# Miscellaneous.net
KiCad netlist of a schematic drawn in Altium Designer
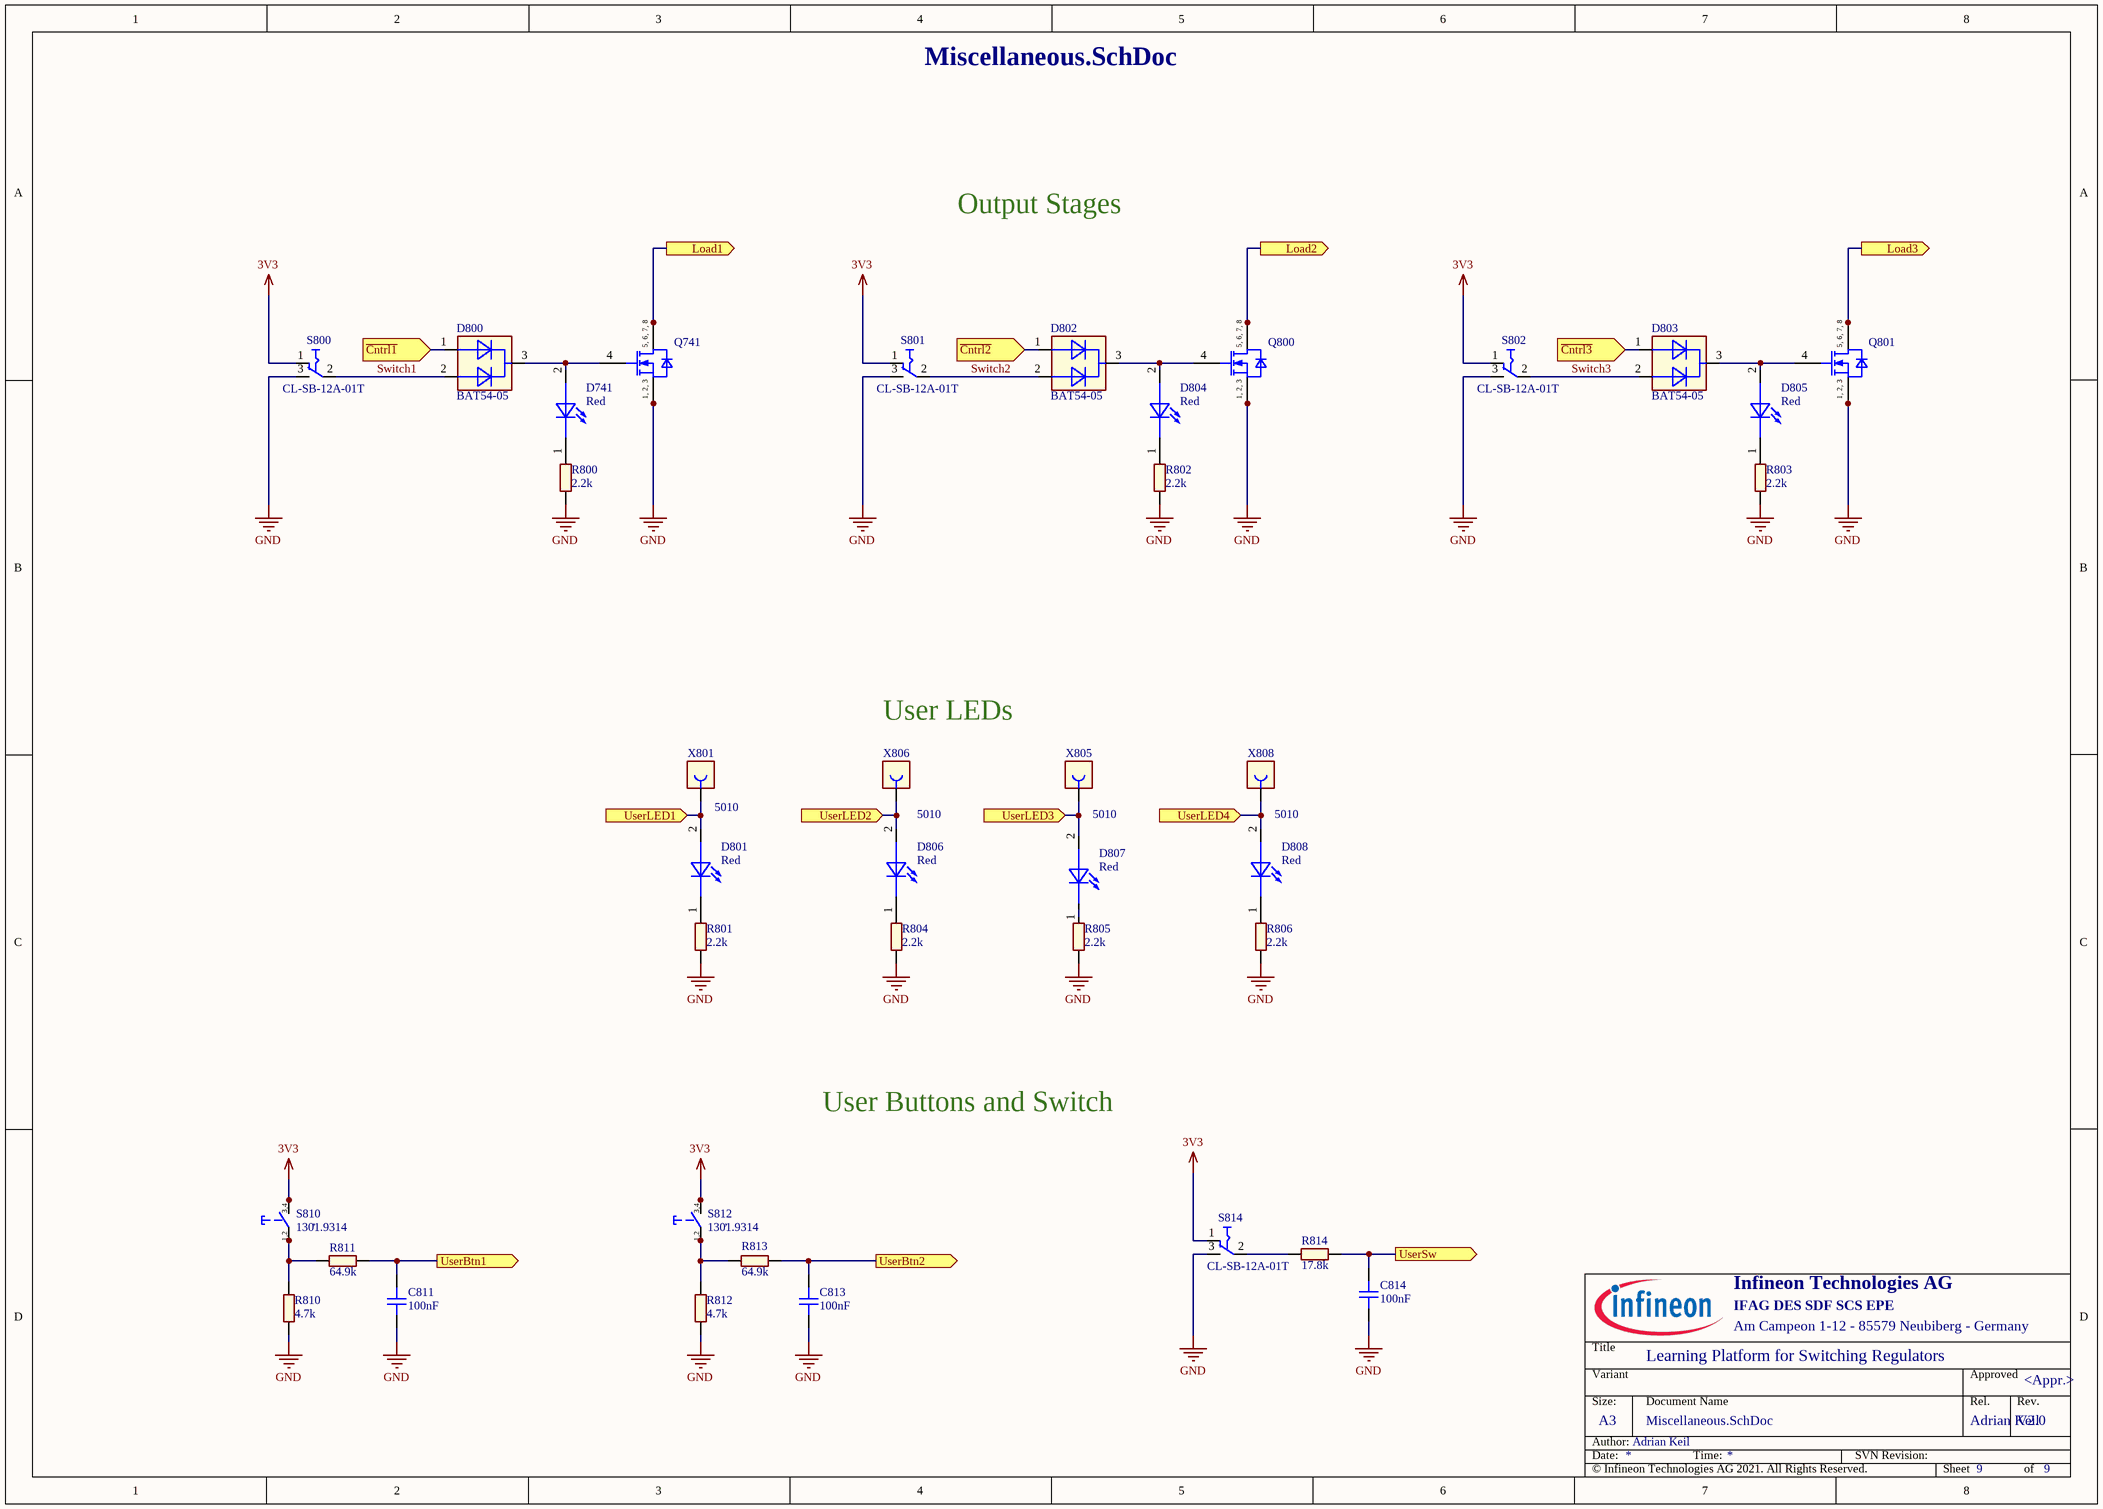
[diagram p0: Miscellaneous.SchDoc]

(export (version "E")
  (design (tool "Eeschema 10.0.6"))
  (components
    (comp (ref "C811")
      (value "100nF")
      (footprint "CAPC3216X125N-0")
      (description "CAP / CERA / 100nF / 50V / 10% / X7R (EIA) / -55°C to 125°C / 1206(3216) / SMD / -")
      (fields (field (name "LEGACY PARTNUMBER") "CAP01005660") (field (name "MANUFACTURER") "MuRata"))
      (libsource (lib "PCBLibraryData") (part "CAP-SGL-STD-02P_00000001"))
    )
    (comp (ref "C813")
      (value "100nF")
      (footprint "CAPC3216X125N-0")
      (description "CAP / CERA / 100nF / 50V / 10% / X7R (EIA) / -55°C to 125°C / 1206(3216) / SMD / -")
      (fields (field (name "LEGACY PARTNUMBER") "CAP01005660") (field (name "MANUFACTURER") "MuRata"))
      (libsource (lib "PCBLibraryData") (part "CAP-SGL-STD-02P_00000001"))
    )
    (comp (ref "C814")
      (value "100nF")
      (footprint "CAPC3216X125N-0")
      (description "CAP / CERA / 100nF / 50V / 10% / X7R (EIA) / -55°C to 125°C / 1206(3216) / SMD / -")
      (fields (field (name "LEGACY PARTNUMBER") "CAP01005660") (field (name "MANUFACTURER") "MuRata"))
      (libsource (lib "PCBLibraryData") (part "CAP-SGL-STD-02P_00000001"))
    )
    (comp (ref "D741")
      (value "Red")
      (footprint "LEDSC160X80X80-2N-1")
      (description "WL-SMCW SMT Mono-color Chip LED Waterclear, Red,630nm")
      (fields (field (name "MANUFACTURER") "Wurth Elektronik"))
      (libsource (lib "PCBLibraryData") (part "d_led_a"))
    )
    (comp (ref "D800")
      (value "BAT54-05")
      (footprint "SOT95P240X110-3N-1-V")
      (description "Silicon Schottky Diode, LS(nH) 1.8, VR 30V")
      (fields
        (field (name "LEGACY PARTNUMBER") "IFX01401370")
        (field (name "MANUFACTURER") "Infineon Technologies")
      )
      (libsource (lib "PCBLibraryData") (part "d_dual_a1a2c3_3p"))
    )
    (comp (ref "D801")
      (value "Red")
      (footprint "LEDSC160X80X80-2N-1")
      (description "WL-SMCW SMT Mono-color Chip LED Waterclear, Red,630nm")
      (fields (field (name "MANUFACTURER") "Wurth Elektronik"))
      (libsource (lib "PCBLibraryData") (part "d_led_a"))
    )
    (comp (ref "D802")
      (value "BAT54-05")
      (footprint "SOT95P240X110-3N-1-V")
      (description "Silicon Schottky Diode, LS(nH) 1.8, VR 30V")
      (fields
        (field (name "LEGACY PARTNUMBER") "IFX01401370")
        (field (name "MANUFACTURER") "Infineon Technologies")
      )
      (libsource (lib "PCBLibraryData") (part "d_dual_a1a2c3_3p"))
    )
    (comp (ref "D803")
      (value "BAT54-05")
      (footprint "SOT95P240X110-3N-1-V")
      (description "Silicon Schottky Diode, LS(nH) 1.8, VR 30V")
      (fields
        (field (name "LEGACY PARTNUMBER") "IFX01401370")
        (field (name "MANUFACTURER") "Infineon Technologies")
      )
      (libsource (lib "PCBLibraryData") (part "d_dual_a1a2c3_3p"))
    )
    (comp (ref "D804")
      (value "Red")
      (footprint "LEDSC160X80X80-2N-1")
      (description "WL-SMCW SMT Mono-color Chip LED Waterclear, Red,630nm")
      (fields (field (name "MANUFACTURER") "Wurth Elektronik"))
      (libsource (lib "PCBLibraryData") (part "d_led_a"))
    )
    (comp (ref "D805")
      (value "Red")
      (footprint "LEDSC160X80X80-2N-1")
      (description "WL-SMCW SMT Mono-color Chip LED Waterclear, Red,630nm")
      (fields (field (name "MANUFACTURER") "Wurth Elektronik"))
      (libsource (lib "PCBLibraryData") (part "d_led_a"))
    )
    (comp (ref "D806")
      (value "Red")
      (footprint "LEDSC160X80X80-2N-1")
      (description "WL-SMCW SMT Mono-color Chip LED Waterclear, Red,630nm")
      (fields (field (name "MANUFACTURER") "Wurth Elektronik"))
      (libsource (lib "PCBLibraryData") (part "d_led_a"))
    )
    (comp (ref "D807")
      (value "Red")
      (footprint "LEDSC160X80X80-2N-1")
      (description "WL-SMCW SMT Mono-color Chip LED Waterclear, Red,630nm")
      (fields (field (name "MANUFACTURER") "Wurth Elektronik"))
      (libsource (lib "PCBLibraryData") (part "d_led_a"))
    )
    (comp (ref "D808")
      (value "Red")
      (footprint "LEDSC160X80X80-2N-1")
      (description "WL-SMCW SMT Mono-color Chip LED Waterclear, Red,630nm")
      (fields (field (name "MANUFACTURER") "Wurth Elektronik"))
      (libsource (lib "PCBLibraryData") (part "d_led_a"))
    )
    (comp (ref "Q741")
      (value "igfet_n_ch_enh_dio_1s2s3s4g5d6d7d8d_8p")
      (footprint "IFX-PG-TDSON-8-6-V")
      (description "OptiMOS Power MOSFET, 30V")
      (fields (field (name "MANUFACTURER") "Infineon Technologies"))
      (libsource (lib "PCBLibraryData") (part "igfet_n_ch_enh_dio_1s2s3s4g5d6d7d8d_8p"))
    )
    (comp (ref "Q800")
      (value "igfet_n_ch_enh_dio_1s2s3s4g5d6d7d8d_8p")
      (footprint "IFX-PG-TDSON-8-6-V")
      (description "OptiMOS Power MOSFET, 30V")
      (fields (field (name "MANUFACTURER") "Infineon Technologies"))
      (libsource (lib "PCBLibraryData") (part "igfet_n_ch_enh_dio_1s2s3s4g5d6d7d8d_8p"))
    )
    (comp (ref "Q801")
      (value "igfet_n_ch_enh_dio_1s2s3s4g5d6d7d8d_8p")
      (footprint "IFX-PG-TDSON-8-6-V")
      (description "OptiMOS Power MOSFET, 30V")
      (fields (field (name "MANUFACTURER") "Infineon Technologies"))
      (libsource (lib "PCBLibraryData") (part "igfet_n_ch_enh_dio_1s2s3s4g5d6d7d8d_8p"))
    )
    (comp (ref "R800")
      (value "2.2k")
      (footprint "RESC3216X60N")
      (description "RES / STD / 2.2k / 250mW / 1% / 100ppm/K / -55°C to 155°C / 1206(3216) / SMD / -")
      (fields (field (name "LEGACY PARTNUMBER") "RES01802779") (field (name "MANUFACTURER") "Vishay"))
      (libsource (lib "PCBLibraryData") (part "RES-SGL-STD-02P_00000006"))
    )
    (comp (ref "R801")
      (value "2.2k")
      (footprint "RESC3216X60N")
      (description "RES / STD / 2.2k / 250mW / 1% / 100ppm/K / -55°C to 155°C / 1206(3216) / SMD / -")
      (fields (field (name "LEGACY PARTNUMBER") "RES01802779") (field (name "MANUFACTURER") "Vishay"))
      (libsource (lib "PCBLibraryData") (part "RES-SGL-STD-02P_00000006"))
    )
    (comp (ref "R802")
      (value "2.2k")
      (footprint "RESC3216X60N")
      (description "RES / STD / 2.2k / 250mW / 1% / 100ppm/K / -55°C to 155°C / 1206(3216) / SMD / -")
      (fields (field (name "LEGACY PARTNUMBER") "RES01802779") (field (name "MANUFACTURER") "Vishay"))
      (libsource (lib "PCBLibraryData") (part "RES-SGL-STD-02P_00000006"))
    )
    (comp (ref "R803")
      (value "2.2k")
      (footprint "RESC3216X60N")
      (description "RES / STD / 2.2k / 250mW / 1% / 100ppm/K / -55°C to 155°C / 1206(3216) / SMD / -")
      (fields (field (name "LEGACY PARTNUMBER") "RES01802779") (field (name "MANUFACTURER") "Vishay"))
      (libsource (lib "PCBLibraryData") (part "RES-SGL-STD-02P_00000006"))
    )
    (comp (ref "R804")
      (value "2.2k")
      (footprint "RESC3216X60N")
      (description "RES / STD / 2.2k / 250mW / 1% / 100ppm/K / -55°C to 155°C / 1206(3216) / SMD / -")
      (fields (field (name "LEGACY PARTNUMBER") "RES01802779") (field (name "MANUFACTURER") "Vishay"))
      (libsource (lib "PCBLibraryData") (part "RES-SGL-STD-02P_00000006"))
    )
    (comp (ref "R805")
      (value "2.2k")
      (footprint "RESC3216X60N")
      (description "RES / STD / 2.2k / 250mW / 1% / 100ppm/K / -55°C to 155°C / 1206(3216) / SMD / -")
      (fields (field (name "LEGACY PARTNUMBER") "RES01802779") (field (name "MANUFACTURER") "Vishay"))
      (libsource (lib "PCBLibraryData") (part "RES-SGL-STD-02P_00000006"))
    )
    (comp (ref "R806")
      (value "2.2k")
      (footprint "RESC3216X60N")
      (description "RES / STD / 2.2k / 250mW / 1% / 100ppm/K / -55°C to 155°C / 1206(3216) / SMD / -")
      (fields (field (name "LEGACY PARTNUMBER") "RES01802779") (field (name "MANUFACTURER") "Vishay"))
      (libsource (lib "PCBLibraryData") (part "RES-SGL-STD-02P_00000006"))
    )
    (comp (ref "R810")
      (value "4.7k")
      (footprint "RESC3216X60N")
      (description "RES / STD / 4.7k / 250mW / 1% / 100ppm/K / -55°C to 155°C / 1206(3216) / SMD / -")
      (fields (field (name "LEGACY PARTNUMBER") "RES01802819") (field (name "MANUFACTURER") "Vishay"))
      (libsource (lib "PCBLibraryData") (part "RES-SGL-STD-02P_00000006"))
    )
    (comp (ref "R811")
      (value "64.9k")
      (footprint "RESC3216X60N")
      (description "RES / STD / 64.9k / 250mW / 1% / 100ppm/K / -55°C to 155°C / 1206(3216) / SMD / -")
      (fields (field (name "LEGACY PARTNUMBER") "RES01802950") (field (name "MANUFACTURER") "Vishay"))
      (libsource (lib "") (part "RES-SGL-STD-02P_00000006_1"))
    )
    (comp (ref "R812")
      (value "4.7k")
      (footprint "RESC3216X60N")
      (description "RES / STD / 4.7k / 250mW / 1% / 100ppm/K / -55°C to 155°C / 1206(3216) / SMD / -")
      (fields (field (name "LEGACY PARTNUMBER") "RES01802819") (field (name "MANUFACTURER") "Vishay"))
      (libsource (lib "PCBLibraryData") (part "RES-SGL-STD-02P_00000006"))
    )
    (comp (ref "R813")
      (value "64.9k")
      (footprint "RESC3216X60N")
      (description "RES / STD / 64.9k / 250mW / 1% / 100ppm/K / -55°C to 155°C / 1206(3216) / SMD / -")
      (fields (field (name "LEGACY PARTNUMBER") "RES01802950") (field (name "MANUFACTURER") "Vishay"))
      (libsource (lib "") (part "RES-SGL-STD-02P_00000006_1"))
    )
    (comp (ref "R814")
      (value "17.8k")
      (footprint "RESC3216X60N")
      (description "RES / STD / 17.8k / 250mW / 1% / 100ppm/K / -55°C to 155°C / 1206(3216) / SMD / -")
      (fields (field (name "LEGACY PARTNUMBER") "RES01802883") (field (name "MANUFACTURER") "Vishay"))
      (libsource (lib "") (part "RES-SGL-STD-02P_00000006_1"))
    )
    (comp (ref "S800")
      (value "CL-SB-12A-01T")
      (footprint "SW-SMD-CL-SB-12A-01T")
      (description "Slid Switch, 12V, 200mA")
      (fields (field (name "MANUFACTURER") "NIDEC COPAL ELECTRONICS, Inc."))
      (libsource (lib "PCBLibraryData") (part "sw_co213_3p"))
    )
    (comp (ref "S801")
      (value "CL-SB-12A-01T")
      (footprint "SW-SMD-CL-SB-12A-01T")
      (description "Slid Switch, 12V, 200mA")
      (fields (field (name "MANUFACTURER") "NIDEC COPAL ELECTRONICS, Inc."))
      (libsource (lib "PCBLibraryData") (part "sw_co213_3p"))
    )
    (comp (ref "S802")
      (value "CL-SB-12A-01T")
      (footprint "SW-SMD-CL-SB-12A-01T")
      (description "Slid Switch, 12V, 200mA")
      (fields (field (name "MANUFACTURER") "NIDEC COPAL ELECTRONICS, Inc."))
      (libsource (lib "PCBLibraryData") (part "sw_co213_3p"))
    )
    (comp (ref "S810")
      (value "1301.9314")
      (footprint "SW-SMD-1301.9314")
      (description "Pushbutton Tactile Switch, Single Pole Single Throw, 4 Pins")
      (fields (field (name "LEGACY PARTNUMBER") "CON01500305") (field (name "MANUFACTURER") "Schurter"))
      (libsource (lib "PCBLibraryData") (part "sw_sr_no12_34_4p"))
    )
    (comp (ref "S812")
      (value "1301.9314")
      (footprint "SW-SMD-1301.9314")
      (description "Pushbutton Tactile Switch, Single Pole Single Throw, 4 Pins")
      (fields (field (name "LEGACY PARTNUMBER") "CON01500305") (field (name "MANUFACTURER") "Schurter"))
      (libsource (lib "PCBLibraryData") (part "sw_sr_no12_34_4p"))
    )
    (comp (ref "S814")
      (value "CL-SB-12A-01T")
      (footprint "SW-SMD-CL-SB-12A-01T")
      (description "Slid Switch, 12V, 200mA")
      (fields (field (name "MANUFACTURER") "NIDEC COPAL ELECTRONICS, Inc."))
      (libsource (lib "PCBLibraryData") (part "sw_co213_3p"))
    )
    (comp (ref "X801")
      (value "5010")
      (footprint "CON-THT-TP-5010")
      (description "PC Test Point-Multipurpose THT, Red")
      (fields
        (field (name "LEGACY PARTNUMBER") "CON01500529")
        (field (name "MANUFACTURER") "Keystone Electronics Corp.")
      )
      (libsource (lib "PCBLibraryData") (part "connector_1_f"))
    )
    (comp (ref "X805")
      (value "5010")
      (footprint "CON-THT-TP-5010")
      (description "PC Test Point-Multipurpose THT, Red")
      (fields
        (field (name "LEGACY PARTNUMBER") "CON01500529")
        (field (name "MANUFACTURER") "Keystone Electronics Corp.")
      )
      (libsource (lib "PCBLibraryData") (part "connector_1_f"))
    )
    (comp (ref "X806")
      (value "5010")
      (footprint "CON-THT-TP-5010")
      (description "PC Test Point-Multipurpose THT, Red")
      (fields
        (field (name "LEGACY PARTNUMBER") "CON01500529")
        (field (name "MANUFACTURER") "Keystone Electronics Corp.")
      )
      (libsource (lib "PCBLibraryData") (part "connector_1_f"))
    )
    (comp (ref "X808")
      (value "5010")
      (footprint "CON-THT-TP-5010")
      (description "PC Test Point-Multipurpose THT, Red")
      (fields
        (field (name "LEGACY PARTNUMBER") "CON01500529")
        (field (name "MANUFACTURER") "Keystone Electronics Corp.")
      )
      (libsource (lib "PCBLibraryData") (part "connector_1_f"))
    )
  )
  (nets
    (net (code "1") (name "/Cntrl1") (class "Default")
      (node (ref "D800") (pin "1") (pinfunction "ANODE_1_1") (pintype "passive"))
    )
    (net (code "2") (name "/Cntrl2") (class "Default")
      (node (ref "D802") (pin "1") (pinfunction "ANODE_1_1") (pintype "passive"))
    )
    (net (code "3") (name "/Cntrl3") (class "Default")
      (node (ref "D803") (pin "1") (pinfunction "ANODE_1_1") (pintype "passive"))
    )
    (net (code "4") (name "/Load1") (class "Default")
      (node (ref "Q741") (pin "5") (pinfunction "DRAIN_5") (pintype "passive"))
      (node (ref "Q741") (pin "6") (pinfunction "DRAIN_6") (pintype "passive"))
      (node (ref "Q741") (pin "7") (pinfunction "DRAIN_7") (pintype "passive"))
      (node (ref "Q741") (pin "8") (pinfunction "DRAIN_8") (pintype "passive"))
    )
    (net (code "5") (name "/Load2") (class "Default")
      (node (ref "Q800") (pin "5") (pinfunction "DRAIN_5") (pintype "passive"))
      (node (ref "Q800") (pin "6") (pinfunction "DRAIN_6") (pintype "passive"))
      (node (ref "Q800") (pin "7") (pinfunction "DRAIN_7") (pintype "passive"))
      (node (ref "Q800") (pin "8") (pinfunction "DRAIN_8") (pintype "passive"))
    )
    (net (code "6") (name "/Load3") (class "Default")
      (node (ref "Q801") (pin "5") (pinfunction "DRAIN_5") (pintype "passive"))
      (node (ref "Q801") (pin "6") (pinfunction "DRAIN_6") (pintype "passive"))
      (node (ref "Q801") (pin "7") (pinfunction "DRAIN_7") (pintype "passive"))
      (node (ref "Q801") (pin "8") (pinfunction "DRAIN_8") (pintype "passive"))
    )
    (net (code "7") (name "/Switch1") (class "Default")
      (node (ref "D800") (pin "2") (pinfunction "ANODE_2_2") (pintype "passive"))
      (node (ref "S800") (pin "2") (pinfunction "2_2") (pintype "passive"))
    )
    (net (code "8") (name "/Switch2") (class "Default")
      (node (ref "D802") (pin "2") (pinfunction "ANODE_2_2") (pintype "passive"))
      (node (ref "S801") (pin "2") (pinfunction "2_2") (pintype "passive"))
    )
    (net (code "9") (name "/Switch3") (class "Default")
      (node (ref "D803") (pin "2") (pinfunction "ANODE_2_2") (pintype "passive"))
      (node (ref "S802") (pin "2") (pinfunction "2_2") (pintype "passive"))
    )
    (net (code "10") (name "/UserBtn1") (class "Default")
      (node (ref "C811") (pin "2") (pinfunction "2_2") (pintype "passive"))
      (node (ref "R811") (pin "2") (pinfunction "2_2") (pintype "passive"))
    )
    (net (code "11") (name "/UserBtn2") (class "Default")
      (node (ref "C813") (pin "2") (pinfunction "2_2") (pintype "passive"))
      (node (ref "R813") (pin "2") (pinfunction "2_2") (pintype "passive"))
    )
    (net (code "12") (name "/UserLED1") (class "Default")
      (node (ref "D801") (pin "2") (pinfunction "Anode_2") (pintype "passive"))
      (node (ref "X801") (pin "1") (pinfunction "1_1") (pintype "passive"))
    )
    (net (code "13") (name "/UserLED2") (class "Default")
      (node (ref "D806") (pin "2") (pinfunction "Anode_2") (pintype "passive"))
      (node (ref "X806") (pin "1") (pinfunction "1_1") (pintype "passive"))
    )
    (net (code "14") (name "/UserLED3") (class "Default")
      (node (ref "D807") (pin "2") (pinfunction "Anode_2") (pintype "passive"))
      (node (ref "X805") (pin "1") (pinfunction "1_1") (pintype "passive"))
    )
    (net (code "15") (name "/UserLED4") (class "Default")
      (node (ref "D808") (pin "2") (pinfunction "Anode_2") (pintype "passive"))
      (node (ref "X808") (pin "1") (pinfunction "1_1") (pintype "passive"))
    )
    (net (code "16") (name "/UserSw") (class "Default")
      (node (ref "C814") (pin "2") (pinfunction "2_2") (pintype "passive"))
      (node (ref "R814") (pin "2") (pinfunction "2_2") (pintype "passive"))
    )
    (net (code "17") (name "3V3") (class "Default")
      (node (ref "S800") (pin "1") (pinfunction "1_1") (pintype "passive"))
      (node (ref "S801") (pin "1") (pinfunction "1_1") (pintype "passive"))
      (node (ref "S802") (pin "1") (pinfunction "1_1") (pintype "passive"))
      (node (ref "S810") (pin "3") (pinfunction "3_3") (pintype "passive"))
      (node (ref "S810") (pin "4") (pinfunction "4_4") (pintype "passive"))
      (node (ref "S812") (pin "3") (pinfunction "3_3") (pintype "passive"))
      (node (ref "S812") (pin "4") (pinfunction "4_4") (pintype "passive"))
      (node (ref "S814") (pin "1") (pinfunction "1_1") (pintype "passive"))
    )
    (net (code "18") (name "GND") (class "Default")
      (node (ref "C811") (pin "1") (pinfunction "1_1") (pintype "passive"))
      (node (ref "C813") (pin "1") (pinfunction "1_1") (pintype "passive"))
      (node (ref "C814") (pin "1") (pinfunction "1_1") (pintype "passive"))
      (node (ref "Q741") (pin "1") (pinfunction "SOURCE_1") (pintype "passive"))
      (node (ref "Q741") (pin "2") (pinfunction "SOURCE_2") (pintype "passive"))
      (node (ref "Q741") (pin "3") (pinfunction "SOURCE_3") (pintype "passive"))
      (node (ref "Q800") (pin "1") (pinfunction "SOURCE_1") (pintype "passive"))
      (node (ref "Q800") (pin "2") (pinfunction "SOURCE_2") (pintype "passive"))
      (node (ref "Q800") (pin "3") (pinfunction "SOURCE_3") (pintype "passive"))
      (node (ref "Q801") (pin "1") (pinfunction "SOURCE_1") (pintype "passive"))
      (node (ref "Q801") (pin "2") (pinfunction "SOURCE_2") (pintype "passive"))
      (node (ref "Q801") (pin "3") (pinfunction "SOURCE_3") (pintype "passive"))
      (node (ref "R800") (pin "2") (pinfunction "2_2") (pintype "passive"))
      (node (ref "R801") (pin "2") (pinfunction "2_2") (pintype "passive"))
      (node (ref "R802") (pin "2") (pinfunction "2_2") (pintype "passive"))
      (node (ref "R803") (pin "2") (pinfunction "2_2") (pintype "passive"))
      (node (ref "R804") (pin "2") (pinfunction "2_2") (pintype "passive"))
      (node (ref "R805") (pin "2") (pinfunction "2_2") (pintype "passive"))
      (node (ref "R806") (pin "2") (pinfunction "2_2") (pintype "passive"))
      (node (ref "R810") (pin "2") (pinfunction "2_2") (pintype "passive"))
      (node (ref "R812") (pin "2") (pinfunction "2_2") (pintype "passive"))
      (node (ref "S800") (pin "3") (pinfunction "3_3") (pintype "passive"))
      (node (ref "S801") (pin "3") (pinfunction "3_3") (pintype "passive"))
      (node (ref "S802") (pin "3") (pinfunction "3_3") (pintype "passive"))
      (node (ref "S814") (pin "3") (pinfunction "3_3") (pintype "passive"))
    )
    (net (code "19") (name "Net-(D741-Anode)") (class "Default")
      (node (ref "D741") (pin "2") (pinfunction "Anode_2") (pintype "passive"))
      (node (ref "D800") (pin "3") (pinfunction "CATHODE_3") (pintype "passive"))
      (node (ref "Q741") (pin "4") (pinfunction "GATE_4") (pintype "passive"))
    )
    (net (code "20") (name "Net-(D741-Cathode)") (class "Default")
      (node (ref "D741") (pin "1") (pinfunction "Cathode_1") (pintype "passive"))
      (node (ref "R800") (pin "1") (pinfunction "1_1") (pintype "passive"))
    )
    (net (code "21") (name "Net-(D801-Cathode)") (class "Default")
      (node (ref "D801") (pin "1") (pinfunction "Cathode_1") (pintype "passive"))
      (node (ref "R801") (pin "1") (pinfunction "1_1") (pintype "passive"))
    )
    (net (code "22") (name "Net-(D802-CATHODE)") (class "Default")
      (node (ref "D802") (pin "3") (pinfunction "CATHODE_3") (pintype "passive"))
      (node (ref "D804") (pin "2") (pinfunction "Anode_2") (pintype "passive"))
      (node (ref "Q800") (pin "4") (pinfunction "GATE_4") (pintype "passive"))
    )
    (net (code "23") (name "Net-(D803-CATHODE)") (class "Default")
      (node (ref "D803") (pin "3") (pinfunction "CATHODE_3") (pintype "passive"))
      (node (ref "D805") (pin "2") (pinfunction "Anode_2") (pintype "passive"))
      (node (ref "Q801") (pin "4") (pinfunction "GATE_4") (pintype "passive"))
    )
    (net (code "24") (name "Net-(D804-Cathode)") (class "Default")
      (node (ref "D804") (pin "1") (pinfunction "Cathode_1") (pintype "passive"))
      (node (ref "R802") (pin "1") (pinfunction "1_1") (pintype "passive"))
    )
    (net (code "25") (name "Net-(D805-Cathode)") (class "Default")
      (node (ref "D805") (pin "1") (pinfunction "Cathode_1") (pintype "passive"))
      (node (ref "R803") (pin "1") (pinfunction "1_1") (pintype "passive"))
    )
    (net (code "26") (name "Net-(D806-Cathode)") (class "Default")
      (node (ref "D806") (pin "1") (pinfunction "Cathode_1") (pintype "passive"))
      (node (ref "R804") (pin "1") (pinfunction "1_1") (pintype "passive"))
    )
    (net (code "27") (name "Net-(D807-Cathode)") (class "Default")
      (node (ref "D807") (pin "1") (pinfunction "Cathode_1") (pintype "passive"))
      (node (ref "R805") (pin "1") (pinfunction "1_1") (pintype "passive"))
    )
    (net (code "28") (name "Net-(D808-Cathode)") (class "Default")
      (node (ref "D808") (pin "1") (pinfunction "Cathode_1") (pintype "passive"))
      (node (ref "R806") (pin "1") (pinfunction "1_1") (pintype "passive"))
    )
    (net (code "29") (name "Net-(R810-Pad1)") (class "Default")
      (node (ref "R810") (pin "1") (pinfunction "1_1") (pintype "passive"))
      (node (ref "R811") (pin "1") (pinfunction "1_1") (pintype "passive"))
      (node (ref "S810") (pin "1") (pinfunction "1_1") (pintype "passive"))
      (node (ref "S810") (pin "2") (pinfunction "2_2") (pintype "passive"))
    )
    (net (code "30") (name "Net-(R812-Pad1)") (class "Default")
      (node (ref "R812") (pin "1") (pinfunction "1_1") (pintype "passive"))
      (node (ref "R813") (pin "1") (pinfunction "1_1") (pintype "passive"))
      (node (ref "S812") (pin "1") (pinfunction "1_1") (pintype "passive"))
      (node (ref "S812") (pin "2") (pinfunction "2_2") (pintype "passive"))
    )
    (net (code "31") (name "Net-(R814-Pad1)") (class "Default")
      (node (ref "R814") (pin "1") (pinfunction "1_1") (pintype "passive"))
      (node (ref "S814") (pin "2") (pinfunction "2_2") (pintype "passive"))
    )
  )
)
